# SolderController.net
KiCad netlist of a schematic drawn in EAGLE
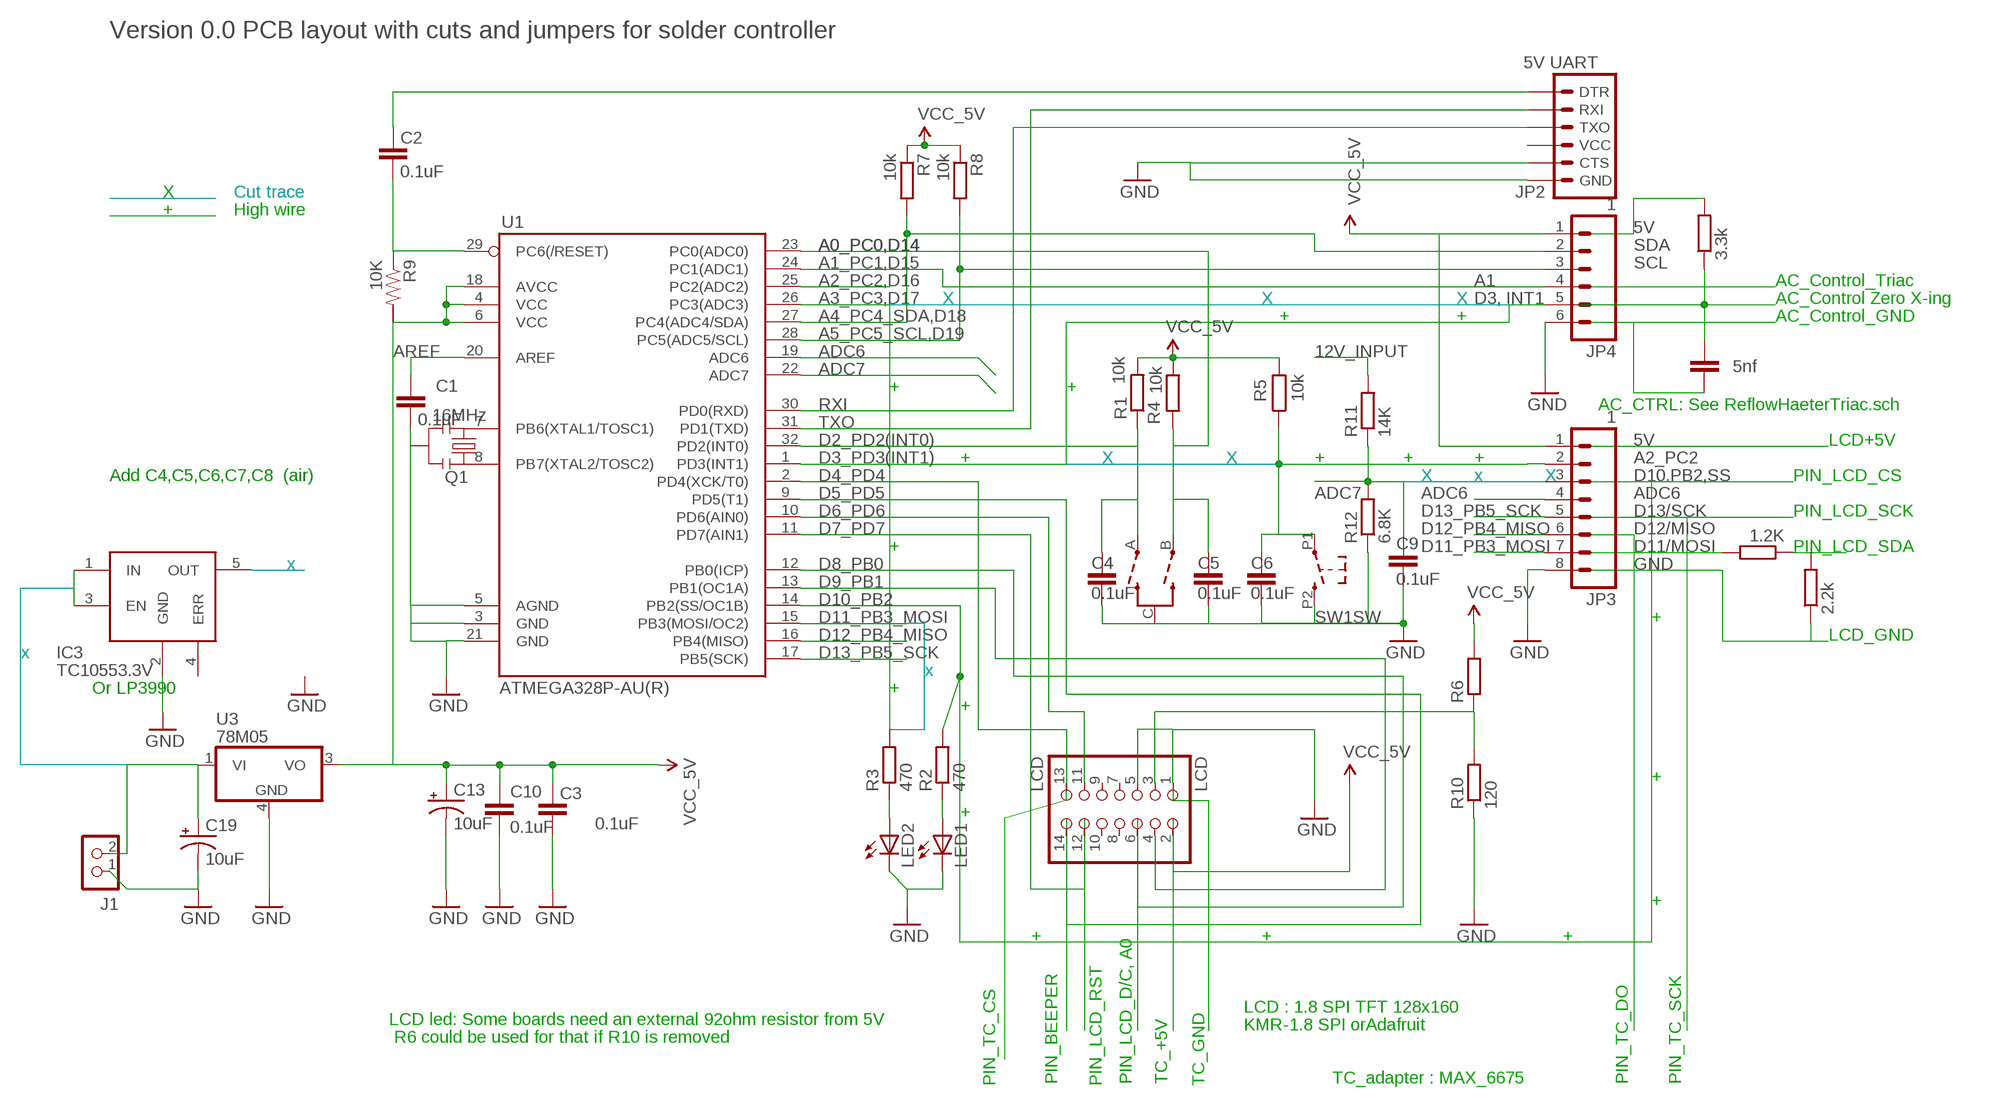
[diagram p0: schematic, sheet 1]

(export (version "E")
  (design (tool "Eeschema 10.0.6"))
  (components
    (comp (ref "C1")
      (value "0.1uF")
      (footprint "eagle-import:0805")
      (libsource (lib "eagle-import") (part "CAP0805"))
    )
    (comp (ref "C2")
      (value "0.1uF")
      (footprint "eagle-import:0805")
      (libsource (lib "eagle-import") (part "CAP0805"))
    )
    (comp (ref "C3")
      (value "0.1uF")
      (footprint "eagle-import:0805")
      (libsource (lib "eagle-import") (part "CAP0805"))
    )
    (comp (ref "C4")
      (value "0.1uF")
      (footprint "eagle-import:0805")
      (libsource (lib "eagle-import") (part "CAP0805"))
    )
    (comp (ref "C5")
      (value "0.1uF")
      (footprint "eagle-import:0805")
      (libsource (lib "eagle-import") (part "CAP0805"))
    )
    (comp (ref "C6")
      (value "0.1uF")
      (footprint "eagle-import:0805")
      (libsource (lib "eagle-import") (part "CAP0805"))
    )
    (comp (ref "C7")
      (value "5nf")
      (footprint "eagle-import:0805")
      (libsource (lib "eagle-import") (part "CAP0805"))
    )
    (comp (ref "C9")
      (value "0.1uF")
      (footprint "eagle-import:0805")
      (libsource (lib "eagle-import") (part "CAP0805"))
    )
    (comp (ref "C10")
      (value "0.1uF")
      (footprint "eagle-import:0805")
      (libsource (lib "eagle-import") (part "CAP0805"))
    )
    (comp (ref "C13")
      (value "10uF")
      (footprint "eagle-import:EIA3216")
      (libsource (lib "eagle-import") (part "CAP_POL1206"))
    )
    (comp (ref "C19")
      (value "10uF")
      (footprint "eagle-import:EIA7343")
      (libsource (lib "eagle-import") (part "CAP_POL7343"))
    )
    (comp (ref "IC3")
      (value "TC10553.3V")
      (footprint "eagle-import:SOT23-5")
      (libsource (lib "eagle-import") (part "TC10553.3V"))
    )
    (comp (ref "J1")
      (value "12V input")
      (footprint "eagle-import:M1X2")
      (libsource (lib "eagle-import") (part "CON_HEADER_1X02-PTH"))
    )
    (comp (ref "JP2")
      (value "5V UART")
      (footprint "eagle-import:1X06")
      (libsource (lib "eagle-import") (part "ARDUINO_SERIAL_PROGRAMPTH"))
    )
    (comp (ref "JP3")
      (value "1")
      (footprint "eagle-import:1X08")
      (libsource (lib "eagle-import") (part "M081X08"))
    )
    (comp (ref "JP4")
      (value "1")
      (footprint "eagle-import:1X06")
      (libsource (lib "eagle-import") (part "M06SIP"))
    )
    (comp (ref "LCD")
      (value "LCD")
      (footprint "eagle-import:2X07")
      (libsource (lib "eagle-import") (part "PINHD-2X7"))
    )
    (comp (ref "LED1")
      (value "LED-5MM")
      (footprint "eagle-import:LED-5MM")
      (libsource (lib "eagle-import") (part "LED-5MM"))
    )
    (comp (ref "LED2")
      (value "LED-5MM")
      (footprint "eagle-import:LED-5MM")
      (libsource (lib "eagle-import") (part "LED-5MM"))
    )
    (comp (ref "Q1")
      (value "16MHz")
      (footprint "eagle-import:RESONATOR-SMD")
      (libsource (lib "eagle-import") (part "RESONATORSMD"))
    )
    (comp (ref "R1")
      (value "10k")
      (footprint "eagle-import:R603")
      (libsource (lib "eagle-import") (part "RESISTOR-0603"))
    )
    (comp (ref "R2")
      (value "470")
      (footprint "eagle-import:R603")
      (libsource (lib "eagle-import") (part "RESISTOR-0603"))
    )
    (comp (ref "R3")
      (value "470")
      (footprint "eagle-import:R603")
      (libsource (lib "eagle-import") (part "RESISTOR-0603"))
    )
    (comp (ref "R4")
      (value "10k")
      (footprint "eagle-import:R603")
      (libsource (lib "eagle-import") (part "RESISTOR-0603"))
    )
    (comp (ref "R5")
      (value "10k")
      (footprint "eagle-import:R603")
      (libsource (lib "eagle-import") (part "RESISTOR-0603"))
    )
    (comp (ref "R6")
      (value "RESISTOR-0603")
      (footprint "eagle-import:R603")
      (libsource (lib "eagle-import") (part "RESISTOR-0603"))
    )
    (comp (ref "R7")
      (value "10k")
      (footprint "eagle-import:R603")
      (libsource (lib "eagle-import") (part "RESISTOR-0603"))
    )
    (comp (ref "R8")
      (value "10k")
      (footprint "eagle-import:R603")
      (libsource (lib "eagle-import") (part "RESISTOR-0603"))
    )
    (comp (ref "R9")
      (value "10K")
      (footprint "eagle-import:0603")
      (libsource (lib "eagle-import") (part "RESISTOR0603"))
    )
    (comp (ref "R10")
      (value "120")
      (footprint "eagle-import:R603")
      (libsource (lib "eagle-import") (part "RESISTOR-0603"))
    )
    (comp (ref "R11")
      (value "14K")
      (footprint "eagle-import:R603")
      (libsource (lib "eagle-import") (part "RESISTOR-0603"))
    )
    (comp (ref "R12")
      (value "6.8K")
      (footprint "eagle-import:R603")
      (libsource (lib "eagle-import") (part "RESISTOR-0603"))
    )
    (comp (ref "R13")
      (value "1.2K")
      (footprint "eagle-import:R603")
      (libsource (lib "eagle-import") (part "RESISTOR-0603"))
    )
    (comp (ref "R14")
      (value "2.2k")
      (footprint "eagle-import:R603")
      (libsource (lib "eagle-import") (part "RESISTOR-0603"))
    )
    (comp (ref "R15")
      (value "3.3k")
      (footprint "eagle-import:R603")
      (libsource (lib "eagle-import") (part "RESISTOR-0603"))
    )
    (comp (ref "SW1")
      (value "ENCODER_SW1-PEC12")
      (footprint "eagle-import:PEC12_INCREMENTAL_ENCODER")
      (libsource (lib "eagle-import") (part "ENCODER_SW1-PEC12"))
    )
    (comp (ref "U1")
      (value "ATMEGA328P-AU(R)")
      (footprint "eagle-import:TQFP32-08")
      (libsource (lib "eagle-import") (part "ATMEGA168"))
    )
    (comp (ref "U3")
      (value "78M05")
      (footprint "eagle-import:DPACK")
      (libsource (lib "eagle-import") (part "78MXXL"))
    )
  )
  (nets
    (net (code "1") (name "/12V_INPUT") (class "Default")
      (node (ref "C19") (pin "A") (pinfunction "+_A") (pintype "passive"))
      (node (ref "J1") (pin "2") (pinfunction "2_2") (pintype "passive"))
      (node (ref "R11") (pin "2") (pinfunction "2_2") (pintype "passive"))
      (node (ref "U3") (pin "1") (pinfunction "VI_1") (pintype "input"))
    )
    (net (code "2") (name "/A0_PC0,D14") (class "Default")
      (node (ref "C5") (pin "2") (pinfunction "2_2") (pintype "passive"))
      (node (ref "R4") (pin "2") (pinfunction "2_2") (pintype "passive"))
      (node (ref "SW1") (pin "B") (pinfunction "B_B") (pintype "passive"))
      (node (ref "U1") (pin "23") (pinfunction "PC0(ADC0)_23") (pintype "bidirectional"))
    )
    (net (code "3") (name "/A1_PC1,D15") (class "Default")
      (node (ref "JP4") (pin "4") (pinfunction "4_4") (pintype "passive"))
      (node (ref "U1") (pin "24") (pinfunction "PC1(ADC1)_24") (pintype "bidirectional"))
    )
    (net (code "4") (name "/A2_PC2") (class "Default")
      (node (ref "JP3") (pin "2") (pinfunction "2_2") (pintype "passive"))
    )
    (net (code "5") (name "/A2_PC2,D16") (class "Default")
      (node (ref "U1") (pin "25") (pinfunction "PC2(ADC2)_25") (pintype "bidirectional"))
    )
    (net (code "6") (name "/A3_PC3,D17") (class "Default")
      (node (ref "U1") (pin "26") (pinfunction "PC3(ADC3)_26") (pintype "bidirectional"))
    )
    (net (code "7") (name "/A4_PC4_SDA,D18") (class "Default")
      (node (ref "JP4") (pin "2") (pinfunction "2_2") (pintype "passive"))
      (node (ref "R7") (pin "2") (pinfunction "2_2") (pintype "passive"))
      (node (ref "U1") (pin "27") (pinfunction "PC4(ADC4/SDA)_27") (pintype "bidirectional"))
    )
    (net (code "8") (name "/A5_PC5_SCL,D19") (class "Default")
      (node (ref "JP4") (pin "3") (pinfunction "3_3") (pintype "passive"))
      (node (ref "R8") (pin "2") (pinfunction "2_2") (pintype "passive"))
      (node (ref "U1") (pin "28") (pinfunction "PC5(ADC5/SCL)_28") (pintype "bidirectional"))
    )
    (net (code "9") (name "/ADC6") (class "Default")
      (node (ref "JP3") (pin "4") (pinfunction "4_4") (pintype "passive"))
      (node (ref "U1") (pin "19") (pinfunction "ADC6_19") (pintype "bidirectional"))
    )
    (net (code "10") (name "/ADC7") (class "Default")
      (node (ref "C9") (pin "1") (pinfunction "1_1") (pintype "passive"))
      (node (ref "R11") (pin "1") (pinfunction "1_1") (pintype "passive"))
      (node (ref "R12") (pin "2") (pinfunction "2_2") (pintype "passive"))
      (node (ref "U1") (pin "22") (pinfunction "ADC7_22") (pintype "bidirectional"))
    )
    (net (code "11") (name "/AREF") (class "Default")
      (node (ref "C1") (pin "2") (pinfunction "2_2") (pintype "passive"))
      (node (ref "U1") (pin "20") (pinfunction "AREF_20") (pintype "bidirectional"))
    )
    (net (code "12") (name "/D2_PD2(INT0)") (class "Default")
      (node (ref "C4") (pin "2") (pinfunction "2_2") (pintype "passive"))
      (node (ref "R1") (pin "1") (pinfunction "1_1") (pintype "passive"))
      (node (ref "SW1") (pin "A") (pinfunction "A_A") (pintype "passive"))
      (node (ref "U1") (pin "32") (pinfunction "PD2(INT0)_32") (pintype "bidirectional"))
    )
    (net (code "13") (name "/D3_PD3(INT1)") (class "Default")
      (node (ref "C6") (pin "2") (pinfunction "2_2") (pintype "passive"))
      (node (ref "R5") (pin "1") (pinfunction "1_1") (pintype "passive"))
      (node (ref "SW1") (pin "P1") (pinfunction "1_P1") (pintype "passive"))
    )
    (net (code "14") (name "/D4_PD4") (class "Default")
      (node (ref "LCD") (pin "13") (pinfunction "13_13") (pintype "passive"))
      (node (ref "U1") (pin "2") (pinfunction "PD4(XCK/T0)_2") (pintype "bidirectional"))
    )
    (net (code "15") (name "/D5_PD5") (class "Default")
      (node (ref "LCD") (pin "14") (pinfunction "14_14") (pintype "passive"))
      (node (ref "U1") (pin "9") (pinfunction "PD5(T1)_9") (pintype "bidirectional"))
    )
    (net (code "16") (name "/D6_PD6") (class "Default")
      (node (ref "LCD") (pin "11") (pinfunction "11_11") (pintype "passive"))
      (node (ref "U1") (pin "10") (pinfunction "PD6(AIN0)_10") (pintype "bidirectional"))
    )
    (net (code "17") (name "/D7_PD7") (class "Default")
      (node (ref "LCD") (pin "12") (pinfunction "12_12") (pintype "passive"))
      (node (ref "U1") (pin "11") (pinfunction "PD7(AIN1)_11") (pintype "bidirectional"))
    )
    (net (code "18") (name "/D8_PB0") (class "Default")
      (node (ref "LCD") (pin "6") (pinfunction "6_6") (pintype "passive"))
      (node (ref "U1") (pin "12") (pinfunction "PB0(ICP)_12") (pintype "bidirectional"))
    )
    (net (code "19") (name "/D9_PB1") (class "Default")
      (node (ref "LCD") (pin "4") (pinfunction "4_4") (pintype "passive"))
      (node (ref "U1") (pin "13") (pinfunction "PB1(OC1A)_13") (pintype "bidirectional"))
    )
    (net (code "20") (name "/D10_PB2") (class "Default")
      (node (ref "R2") (pin "2") (pinfunction "2_2") (pintype "passive"))
      (node (ref "U1") (pin "14") (pinfunction "PB2(SS/OC1B)_14") (pintype "bidirectional"))
    )
    (net (code "21") (name "/D11_PB3_MOSI") (class "Default")
      (node (ref "JP3") (pin "7") (pinfunction "7_7") (pintype "passive"))
      (node (ref "U1") (pin "15") (pinfunction "PB3(MOSI/OC2)_15") (pintype "bidirectional"))
    )
    (net (code "22") (name "/D12_PB4_MISO") (class "Default")
      (node (ref "JP3") (pin "6") (pinfunction "6_6") (pintype "passive"))
      (node (ref "U1") (pin "16") (pinfunction "PB4(MISO)_16") (pintype "bidirectional"))
    )
    (net (code "23") (name "/D13_PB5_SCK") (class "Default")
      (node (ref "JP3") (pin "5") (pinfunction "5_5") (pintype "passive"))
      (node (ref "U1") (pin "17") (pinfunction "PB5(SCK)_17") (pintype "bidirectional"))
    )
    (net (code "24") (name "/OUT") (class "Default")
      (node (ref "IC3") (pin "5") (pinfunction "OUT_5") (pintype "power_in"))
    )
    (net (code "25") (name "/RXI") (class "Default")
      (node (ref "JP2") (pin "3") (pinfunction "TXO_3") (pintype "passive"))
      (node (ref "U1") (pin "30") (pinfunction "PD0(RXD)_30") (pintype "bidirectional"))
    )
    (net (code "26") (name "/TXO") (class "Default")
      (node (ref "JP2") (pin "2") (pinfunction "RXI_2") (pintype "passive"))
      (node (ref "U1") (pin "31") (pinfunction "PD1(TXD)_31") (pintype "bidirectional"))
    )
    (net (code "27") (name "GND") (class "Default")
      (node (ref "C1") (pin "1") (pinfunction "1_1") (pintype "passive"))
      (node (ref "C10") (pin "2") (pinfunction "2_2") (pintype "passive"))
      (node (ref "C13") (pin "C") (pinfunction "-_C") (pintype "passive"))
      (node (ref "C19") (pin "C") (pinfunction "-_C") (pintype "passive"))
      (node (ref "C3") (pin "1") (pinfunction "1_1") (pintype "passive"))
      (node (ref "C4") (pin "1") (pinfunction "1_1") (pintype "passive"))
      (node (ref "C5") (pin "1") (pinfunction "1_1") (pintype "passive"))
      (node (ref "C6") (pin "1") (pinfunction "1_1") (pintype "passive"))
      (node (ref "C9") (pin "2") (pinfunction "2_2") (pintype "passive"))
      (node (ref "IC3") (pin "2") (pinfunction "GND_2") (pintype "power_in"))
      (node (ref "J1") (pin "1") (pinfunction "1_1") (pintype "passive"))
      (node (ref "JP2") (pin "5") (pinfunction "CTS_5") (pintype "passive"))
      (node (ref "JP2") (pin "6") (pinfunction "GND_6") (pintype "passive"))
      (node (ref "JP3") (pin "8") (pinfunction "8_8") (pintype "passive"))
      (node (ref "JP4") (pin "6") (pinfunction "6_6") (pintype "passive"))
      (node (ref "LCD") (pin "1") (pinfunction "1_1") (pintype "passive"))
      (node (ref "LCD") (pin "5") (pinfunction "5_5") (pintype "passive"))
      (node (ref "LED1") (pin "K") (pinfunction "C_K") (pintype "passive"))
      (node (ref "LED2") (pin "K") (pinfunction "C_K") (pintype "passive"))
      (node (ref "Q1") (pin "2") (pinfunction "2_2") (pintype "passive"))
      (node (ref "R10") (pin "1") (pinfunction "1_1") (pintype "passive"))
      (node (ref "R12") (pin "1") (pinfunction "1_1") (pintype "passive"))
      (node (ref "SW1") (pin "C") (pinfunction "C_C") (pintype "passive"))
      (node (ref "SW1") (pin "P2") (pinfunction "2_P2") (pintype "passive"))
      (node (ref "U1") (pin "21") (pinfunction "GND_21") (pintype "bidirectional"))
      (node (ref "U1") (pin "3") (pinfunction "GND_3") (pintype "bidirectional"))
      (node (ref "U1") (pin "5") (pinfunction "AGND_5") (pintype "bidirectional"))
      (node (ref "U3") (pin "4") (pinfunction "GND_4") (pintype "passive"))
    )
    (net (code "28") (name "Net-(IC3-EN)") (class "Default")
      (node (ref "IC3") (pin "1") (pinfunction "IN_1") (pintype "power_in"))
      (node (ref "IC3") (pin "3") (pinfunction "EN_3") (pintype "input"))
    )
    (net (code "29") (name "Net-(JP2-DTR)") (class "Default")
      (node (ref "C2") (pin "2") (pinfunction "2_2") (pintype "passive"))
      (node (ref "JP2") (pin "1") (pinfunction "DTR_1") (pintype "passive"))
    )
    (net (code "30") (name "Net-(LCD-Pad3)") (class "Default")
      (node (ref "LCD") (pin "3") (pinfunction "3_3") (pintype "passive"))
      (node (ref "R10") (pin "2") (pinfunction "2_2") (pintype "passive"))
      (node (ref "R6") (pin "1") (pinfunction "1_1") (pintype "passive"))
    )
    (net (code "31") (name "Net-(LED1-PadA)") (class "Default")
      (node (ref "LED1") (pin "A") (pinfunction "A_A") (pintype "passive"))
      (node (ref "R2") (pin "1") (pinfunction "1_1") (pintype "passive"))
    )
    (net (code "32") (name "Net-(LED2-PadA)") (class "Default")
      (node (ref "LED2") (pin "A") (pinfunction "A_A") (pintype "passive"))
      (node (ref "R3") (pin "1") (pinfunction "1_1") (pintype "passive"))
    )
    (net (code "33") (name "Net-(U1-PB6(XTAL1{slash}TOSC1))") (class "Default")
      (node (ref "Q1") (pin "3") (pinfunction "3_3") (pintype "passive"))
      (node (ref "U1") (pin "7") (pinfunction "PB6(XTAL1/TOSC1)_7") (pintype "bidirectional"))
    )
    (net (code "34") (name "Net-(U1-PB7(XTAL2{slash}TOSC2))") (class "Default")
      (node (ref "Q1") (pin "1") (pinfunction "1_1") (pintype "passive"))
      (node (ref "U1") (pin "8") (pinfunction "PB7(XTAL2/TOSC2)_8") (pintype "bidirectional"))
    )
    (net (code "35") (name "Net-(U1-PC6({slash}RESET))") (class "Default")
      (node (ref "C2") (pin "1") (pinfunction "1_1") (pintype "passive"))
      (node (ref "R9") (pin "1") (pinfunction "1_1") (pintype "passive"))
      (node (ref "U1") (pin "29") (pinfunction "PC6(/RESET)_29") (pintype "bidirectional"))
    )
    (net (code "36") (name "VCC_5V") (class "Default")
      (node (ref "C10") (pin "1") (pinfunction "1_1") (pintype "passive"))
      (node (ref "C13") (pin "A") (pinfunction "+_A") (pintype "passive"))
      (node (ref "C3") (pin "2") (pinfunction "2_2") (pintype "passive"))
      (node (ref "JP3") (pin "1") (pinfunction "1_1") (pintype "passive"))
      (node (ref "JP4") (pin "1") (pinfunction "1_1") (pintype "passive"))
      (node (ref "LCD") (pin "2") (pinfunction "2_2") (pintype "passive"))
      (node (ref "R1") (pin "2") (pinfunction "2_2") (pintype "passive"))
      (node (ref "R4") (pin "1") (pinfunction "1_1") (pintype "passive"))
      (node (ref "R5") (pin "2") (pinfunction "2_2") (pintype "passive"))
      (node (ref "R6") (pin "2") (pinfunction "2_2") (pintype "passive"))
      (node (ref "R7") (pin "1") (pinfunction "1_1") (pintype "passive"))
      (node (ref "R8") (pin "1") (pinfunction "1_1") (pintype "passive"))
      (node (ref "R9") (pin "2") (pinfunction "2_2") (pintype "passive"))
      (node (ref "U1") (pin "18") (pinfunction "AVCC_18") (pintype "bidirectional"))
      (node (ref "U1") (pin "4") (pinfunction "VCC_4") (pintype "bidirectional"))
      (node (ref "U1") (pin "6") (pinfunction "VCC_6") (pintype "bidirectional"))
      (node (ref "U3") (pin "3") (pinfunction "VO_3") (pintype "passive"))
    )
    (net (code "37") (name "unconnected-(C7-Pad1)") (class "Default")
      (node (ref "C7") (pin "1") (pinfunction "1_1") (pintype "passive"))
    )
    (net (code "38") (name "unconnected-(C7-Pad2)") (class "Default")
      (node (ref "C7") (pin "2") (pinfunction "2_2") (pintype "passive"))
    )
    (net (code "39") (name "unconnected-(IC3-ERR-Pad4)") (class "Default")
      (node (ref "IC3") (pin "4") (pinfunction "ERR_4") (pintype "output"))
    )
    (net (code "40") (name "unconnected-(JP2-VCC-Pad4)") (class "Default")
      (node (ref "JP2") (pin "4") (pinfunction "VCC_4") (pintype "passive"))
    )
    (net (code "41") (name "unconnected-(JP3-Pad3)") (class "Default")
      (node (ref "JP3") (pin "3") (pinfunction "3_3") (pintype "passive"))
    )
    (net (code "42") (name "unconnected-(JP4-Pad5)") (class "Default")
      (node (ref "JP4") (pin "5") (pinfunction "5_5") (pintype "passive"))
    )
    (net (code "43") (name "unconnected-(LCD-Pad7)") (class "Default")
      (node (ref "LCD") (pin "7") (pinfunction "7_7") (pintype "passive"))
    )
    (net (code "44") (name "unconnected-(LCD-Pad8)") (class "Default")
      (node (ref "LCD") (pin "8") (pinfunction "8_8") (pintype "passive"))
    )
    (net (code "45") (name "unconnected-(LCD-Pad9)") (class "Default")
      (node (ref "LCD") (pin "9") (pinfunction "9_9") (pintype "passive"))
    )
    (net (code "46") (name "unconnected-(LCD-Pad10)") (class "Default")
      (node (ref "LCD") (pin "10") (pinfunction "10_10") (pintype "passive"))
    )
    (net (code "47") (name "unconnected-(R3-Pad2)") (class "Default")
      (node (ref "R3") (pin "2") (pinfunction "2_2") (pintype "passive"))
    )
    (net (code "48") (name "unconnected-(R13-Pad1)") (class "Default")
      (node (ref "R13") (pin "1") (pinfunction "1_1") (pintype "passive"))
    )
    (net (code "49") (name "unconnected-(R13-Pad2)") (class "Default")
      (node (ref "R13") (pin "2") (pinfunction "2_2") (pintype "passive"))
    )
    (net (code "50") (name "unconnected-(R14-Pad1)") (class "Default")
      (node (ref "R14") (pin "1") (pinfunction "1_1") (pintype "passive"))
    )
    (net (code "51") (name "unconnected-(R14-Pad2)") (class "Default")
      (node (ref "R14") (pin "2") (pinfunction "2_2") (pintype "passive"))
    )
    (net (code "52") (name "unconnected-(R15-Pad1)") (class "Default")
      (node (ref "R15") (pin "1") (pinfunction "1_1") (pintype "passive"))
    )
    (net (code "53") (name "unconnected-(R15-Pad2)") (class "Default")
      (node (ref "R15") (pin "2") (pinfunction "2_2") (pintype "passive"))
    )
    (net (code "54") (name "unconnected-(U1-PD3(INT1)-Pad1)") (class "Default")
      (node (ref "U1") (pin "1") (pinfunction "PD3(INT1)_1") (pintype "bidirectional"))
    )
  )
)
